# 11_-_CPU_-_POWER.net
KiCad netlist of a schematic drawn in Altium Designer
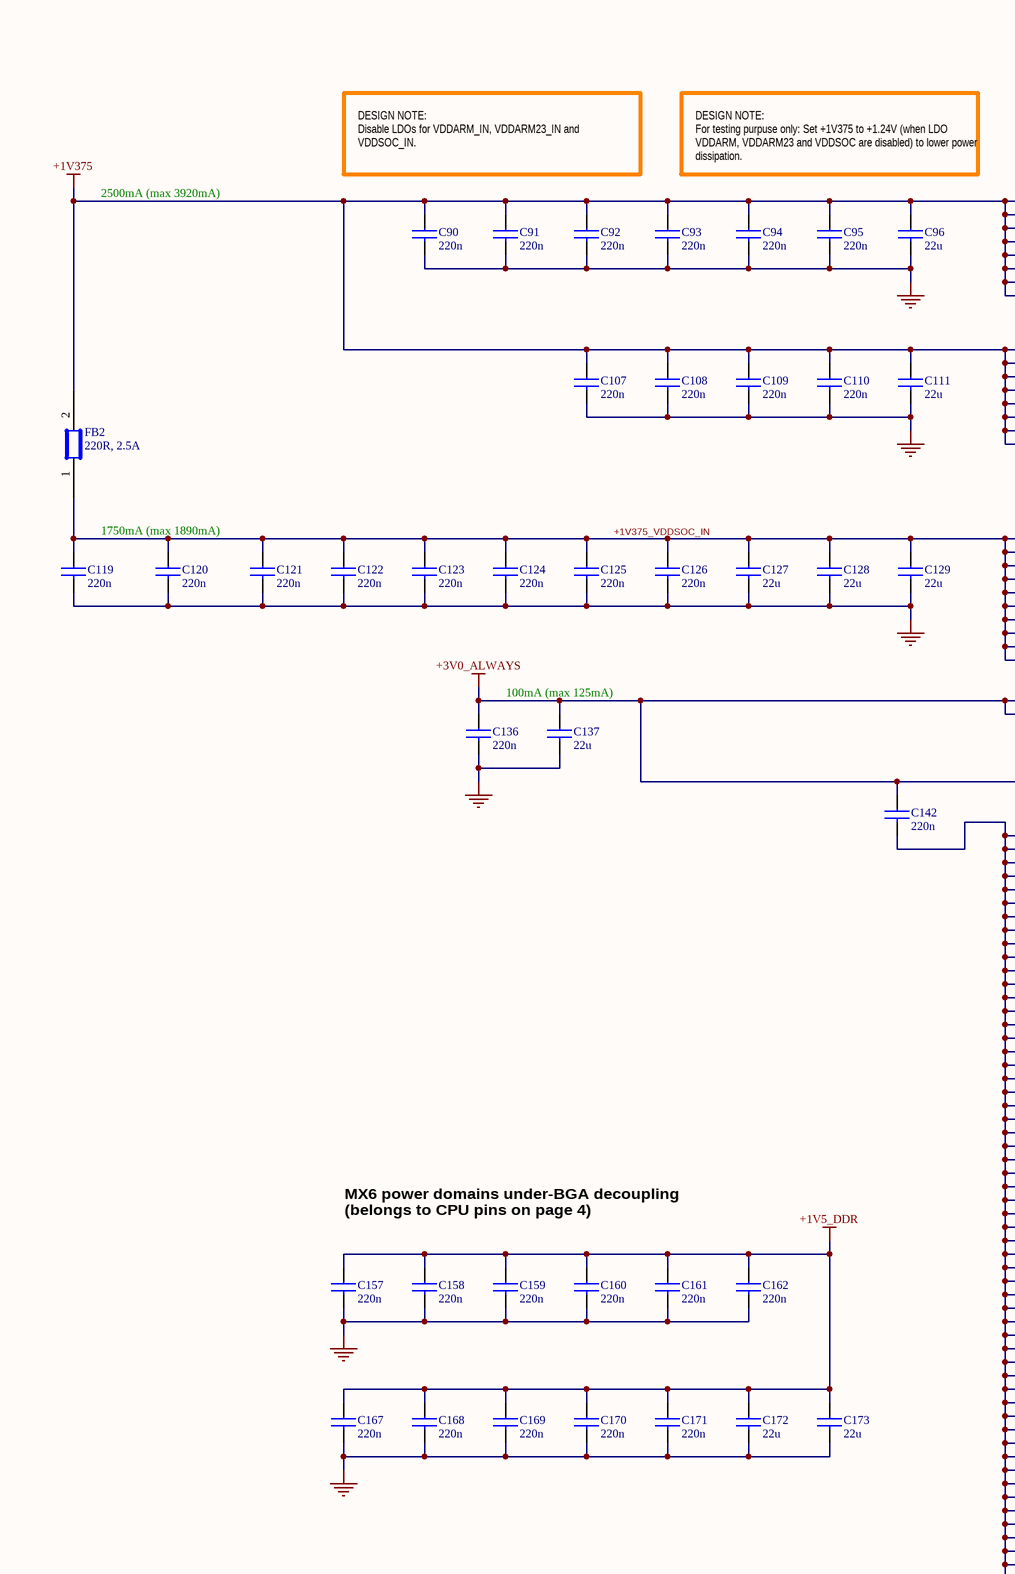
[diagram p0: [11] - CPU - POWER.SchDoc, left]
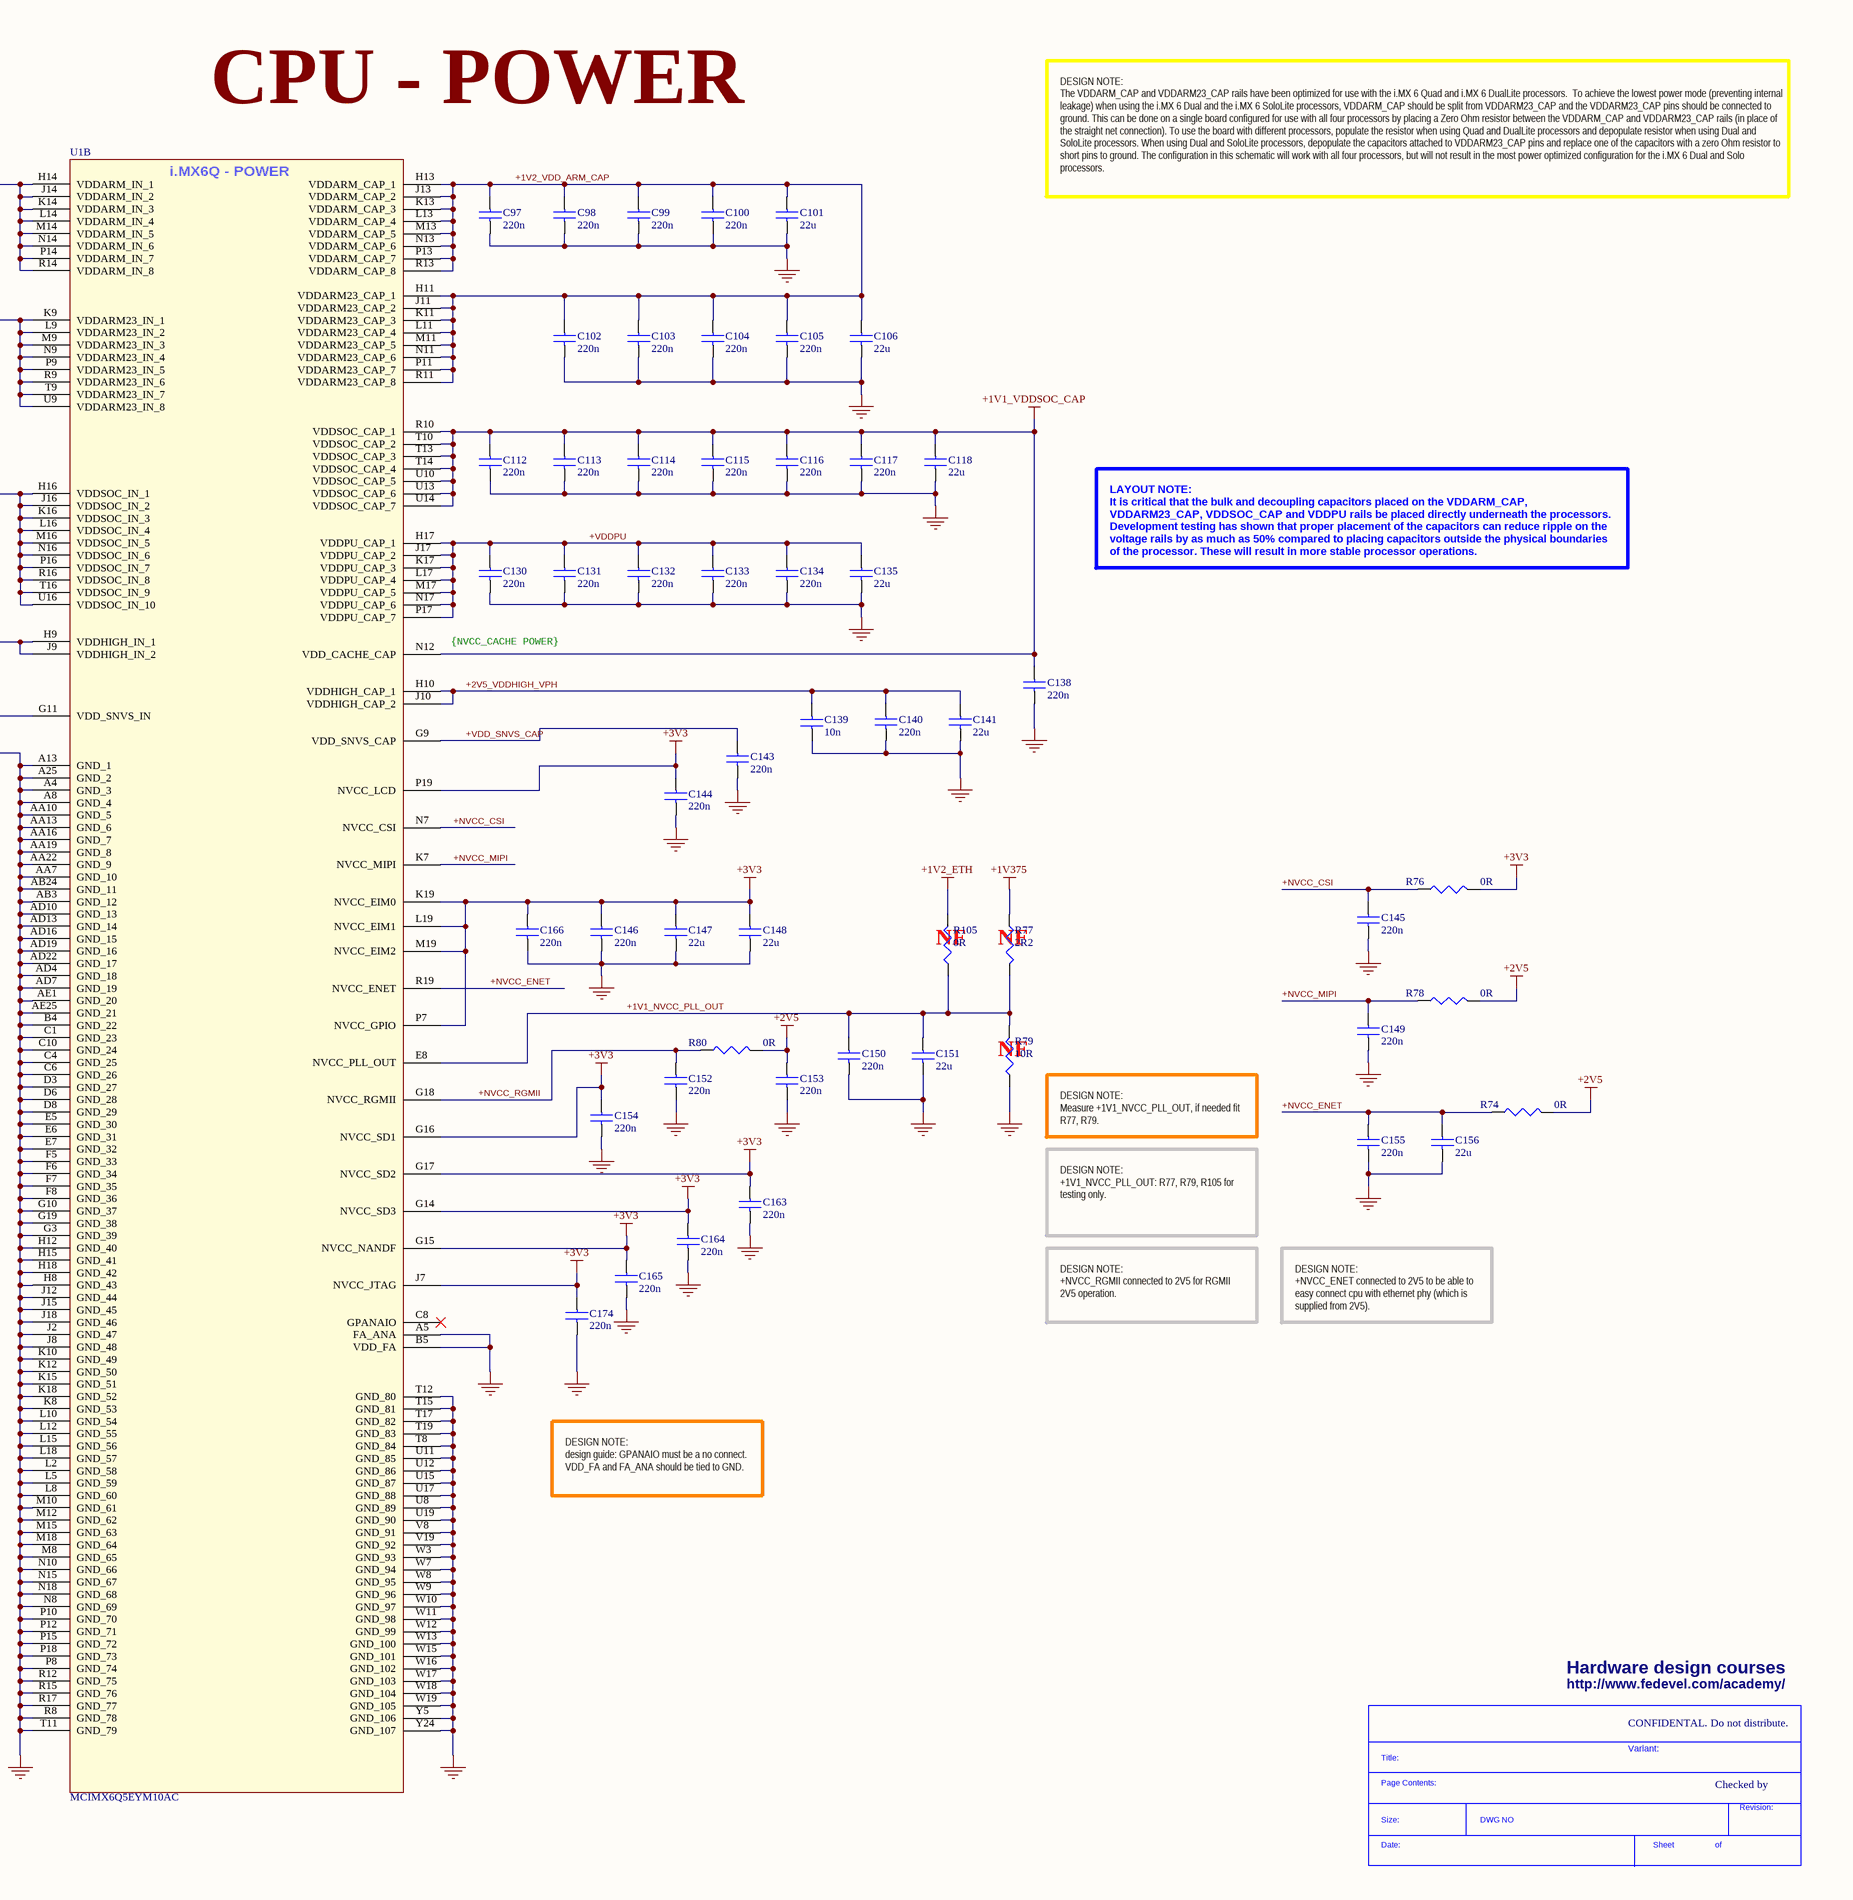
[diagram p1: [11] - CPU - POWER.SchDoc, right]

(export (version "E")
  (design (tool "Eeschema 10.0.6"))
  (components
    (comp (ref "C90")
      (value "220n")
      (footprint "C0402")
      (description "CAP CER .22UF 25V X5R 20% 0402")
      (fields
        (field (name "MANUFACTURER") "TDK Corporation")
        (field (name "MANUFACTURER PART NUMBER") "C1005X5R1E224M")
      )
      (libsource (lib "Integrated_Library_RF_FEB_2012") (part "C1005X5R1E224M"))
    )
    (comp (ref "C91")
      (value "220n")
      (footprint "C0402")
      (description "CAP CER .22UF 25V X5R 20% 0402")
      (fields
        (field (name "MANUFACTURER") "TDK Corporation")
        (field (name "MANUFACTURER PART NUMBER") "C1005X5R1E224M")
      )
      (libsource (lib "Integrated_Library_RF_FEB_2012") (part "C1005X5R1E224M"))
    )
    (comp (ref "C92")
      (value "220n")
      (footprint "C0402")
      (description "CAP CER .22UF 25V X5R 20% 0402")
      (fields
        (field (name "MANUFACTURER") "TDK Corporation")
        (field (name "MANUFACTURER PART NUMBER") "C1005X5R1E224M")
      )
      (libsource (lib "Integrated_Library_RF_FEB_2012") (part "C1005X5R1E224M"))
    )
    (comp (ref "C93")
      (value "220n")
      (footprint "C0402")
      (description "CAP CER .22UF 25V X5R 20% 0402")
      (fields
        (field (name "MANUFACTURER") "TDK Corporation")
        (field (name "MANUFACTURER PART NUMBER") "C1005X5R1E224M")
      )
      (libsource (lib "Integrated_Library_RF_FEB_2012") (part "C1005X5R1E224M"))
    )
    (comp (ref "C94")
      (value "220n")
      (footprint "C0402")
      (description "CAP CER .22UF 25V X5R 20% 0402")
      (fields
        (field (name "MANUFACTURER") "TDK Corporation")
        (field (name "MANUFACTURER PART NUMBER") "C1005X5R1E224M")
      )
      (libsource (lib "Integrated_Library_RF_FEB_2012") (part "C1005X5R1E224M"))
    )
    (comp (ref "C95")
      (value "220n")
      (footprint "C0402")
      (description "CAP CER .22UF 25V X5R 20% 0402")
      (fields
        (field (name "MANUFACTURER") "TDK Corporation")
        (field (name "MANUFACTURER PART NUMBER") "C1005X5R1E224M")
      )
      (libsource (lib "Integrated_Library_RF_FEB_2012") (part "C1005X5R1E224M"))
    )
    (comp (ref "C96")
      (value "22u")
      (footprint "C0603")
      (description "CAP CER 22UF 4V 20% X5R 0603")
      (fields
        (field (name "MANUFACTURER") "Murata Electronics North America")
        (field (name "MANUFACTURER PART NUMBER") "GRM188R60G226MEA0L")
        (field (name ".CHECKED PCB") "RF, used by MM")
        (field (name ".CHECKED SCH") "MM, checked by RF")
        (field (name ".CREATOR") "MM")
      )
      (libsource (lib "Schlib_RF") (part "GRM188R60G226MEA0L"))
    )
    (comp (ref "C97")
      (value "220n")
      (footprint "C0402")
      (description "CAP CER .22UF 25V X5R 20% 0402")
      (fields
        (field (name "MANUFACTURER") "TDK Corporation")
        (field (name "MANUFACTURER PART NUMBER") "C1005X5R1E224M")
      )
      (libsource (lib "Integrated_Library_RF_FEB_2012") (part "C1005X5R1E224M"))
    )
    (comp (ref "C98")
      (value "220n")
      (footprint "C0402")
      (description "CAP CER .22UF 25V X5R 20% 0402")
      (fields
        (field (name "MANUFACTURER") "TDK Corporation")
        (field (name "MANUFACTURER PART NUMBER") "C1005X5R1E224M")
      )
      (libsource (lib "Integrated_Library_RF_FEB_2012") (part "C1005X5R1E224M"))
    )
    (comp (ref "C99")
      (value "220n")
      (footprint "C0402")
      (description "CAP CER .22UF 25V X5R 20% 0402")
      (fields
        (field (name "MANUFACTURER") "TDK Corporation")
        (field (name "MANUFACTURER PART NUMBER") "C1005X5R1E224M")
      )
      (libsource (lib "Integrated_Library_RF_FEB_2012") (part "C1005X5R1E224M"))
    )
    (comp (ref "C100")
      (value "220n")
      (footprint "C0402")
      (description "CAP CER .22UF 25V X5R 20% 0402")
      (fields
        (field (name "MANUFACTURER") "TDK Corporation")
        (field (name "MANUFACTURER PART NUMBER") "C1005X5R1E224M")
      )
      (libsource (lib "Integrated_Library_RF_FEB_2012") (part "C1005X5R1E224M"))
    )
    (comp (ref "C101")
      (value "22u")
      (footprint "C0603")
      (description "CAP CER 22UF 4V 20% X5R 0603")
      (fields
        (field (name "MANUFACTURER") "Murata Electronics North America")
        (field (name "MANUFACTURER PART NUMBER") "GRM188R60G226MEA0L")
        (field (name ".CHECKED PCB") "RF, used by MM")
        (field (name ".CHECKED SCH") "MM, checked by RF")
        (field (name ".CREATOR") "MM")
      )
      (libsource (lib "Schlib_RF") (part "GRM188R60G226MEA0L"))
    )
    (comp (ref "C102")
      (value "220n")
      (footprint "C0402")
      (description "CAP CER .22UF 25V X5R 20% 0402")
      (fields
        (field (name "MANUFACTURER") "TDK Corporation")
        (field (name "MANUFACTURER PART NUMBER") "C1005X5R1E224M")
      )
      (libsource (lib "Integrated_Library_RF_FEB_2012") (part "C1005X5R1E224M"))
    )
    (comp (ref "C103")
      (value "220n")
      (footprint "C0402")
      (description "CAP CER .22UF 25V X5R 20% 0402")
      (fields
        (field (name "MANUFACTURER") "TDK Corporation")
        (field (name "MANUFACTURER PART NUMBER") "C1005X5R1E224M")
      )
      (libsource (lib "Integrated_Library_RF_FEB_2012") (part "C1005X5R1E224M"))
    )
    (comp (ref "C104")
      (value "220n")
      (footprint "C0402")
      (description "CAP CER .22UF 25V X5R 20% 0402")
      (fields
        (field (name "MANUFACTURER") "TDK Corporation")
        (field (name "MANUFACTURER PART NUMBER") "C1005X5R1E224M")
      )
      (libsource (lib "Integrated_Library_RF_FEB_2012") (part "C1005X5R1E224M"))
    )
    (comp (ref "C105")
      (value "220n")
      (footprint "C0402")
      (description "CAP CER .22UF 25V X5R 20% 0402")
      (fields
        (field (name "MANUFACTURER") "TDK Corporation")
        (field (name "MANUFACTURER PART NUMBER") "C1005X5R1E224M")
      )
      (libsource (lib "Integrated_Library_RF_FEB_2012") (part "C1005X5R1E224M"))
    )
    (comp (ref "C106")
      (value "22u")
      (footprint "C0603")
      (description "CAP CER 22UF 4V 20% X5R 0603")
      (fields
        (field (name "MANUFACTURER") "Murata Electronics North America")
        (field (name "MANUFACTURER PART NUMBER") "GRM188R60G226MEA0L")
        (field (name ".CHECKED PCB") "RF, used by MM")
        (field (name ".CHECKED SCH") "MM, checked by RF")
        (field (name ".CREATOR") "MM")
      )
      (libsource (lib "Schlib_RF") (part "GRM188R60G226MEA0L"))
    )
    (comp (ref "C107")
      (value "220n")
      (footprint "C0402")
      (description "CAP CER .22UF 25V X5R 20% 0402")
      (fields
        (field (name "MANUFACTURER") "TDK Corporation")
        (field (name "MANUFACTURER PART NUMBER") "C1005X5R1E224M")
      )
      (libsource (lib "Integrated_Library_RF_FEB_2012") (part "C1005X5R1E224M"))
    )
    (comp (ref "C108")
      (value "220n")
      (footprint "C0402")
      (description "CAP CER .22UF 25V X5R 20% 0402")
      (fields
        (field (name "MANUFACTURER") "TDK Corporation")
        (field (name "MANUFACTURER PART NUMBER") "C1005X5R1E224M")
      )
      (libsource (lib "Integrated_Library_RF_FEB_2012") (part "C1005X5R1E224M"))
    )
    (comp (ref "C109")
      (value "220n")
      (footprint "C0402")
      (description "CAP CER .22UF 25V X5R 20% 0402")
      (fields
        (field (name "MANUFACTURER") "TDK Corporation")
        (field (name "MANUFACTURER PART NUMBER") "C1005X5R1E224M")
      )
      (libsource (lib "Integrated_Library_RF_FEB_2012") (part "C1005X5R1E224M"))
    )
    (comp (ref "C110")
      (value "220n")
      (footprint "C0402")
      (description "CAP CER .22UF 25V X5R 20% 0402")
      (fields
        (field (name "MANUFACTURER") "TDK Corporation")
        (field (name "MANUFACTURER PART NUMBER") "C1005X5R1E224M")
      )
      (libsource (lib "Integrated_Library_RF_FEB_2012") (part "C1005X5R1E224M"))
    )
    (comp (ref "C111")
      (value "22u")
      (footprint "C0603")
      (description "CAP CER 22UF 4V 20% X5R 0603")
      (fields
        (field (name "MANUFACTURER") "Murata Electronics North America")
        (field (name "MANUFACTURER PART NUMBER") "GRM188R60G226MEA0L")
        (field (name ".CHECKED PCB") "RF, used by MM")
        (field (name ".CHECKED SCH") "MM, checked by RF")
        (field (name ".CREATOR") "MM")
      )
      (libsource (lib "Schlib_RF") (part "GRM188R60G226MEA0L"))
    )
    (comp (ref "C112")
      (value "220n")
      (footprint "C0402")
      (description "CAP CER .22UF 25V X5R 20% 0402")
      (fields
        (field (name "MANUFACTURER") "TDK Corporation")
        (field (name "MANUFACTURER PART NUMBER") "C1005X5R1E224M")
      )
      (libsource (lib "Integrated_Library_RF_FEB_2012") (part "C1005X5R1E224M"))
    )
    (comp (ref "C113")
      (value "220n")
      (footprint "C0402")
      (description "CAP CER .22UF 25V X5R 20% 0402")
      (fields
        (field (name "MANUFACTURER") "TDK Corporation")
        (field (name "MANUFACTURER PART NUMBER") "C1005X5R1E224M")
      )
      (libsource (lib "Integrated_Library_RF_FEB_2012") (part "C1005X5R1E224M"))
    )
    (comp (ref "C114")
      (value "220n")
      (footprint "C0402")
      (description "CAP CER .22UF 25V X5R 20% 0402")
      (fields
        (field (name "MANUFACTURER") "TDK Corporation")
        (field (name "MANUFACTURER PART NUMBER") "C1005X5R1E224M")
      )
      (libsource (lib "Integrated_Library_RF_FEB_2012") (part "C1005X5R1E224M"))
    )
    (comp (ref "C115")
      (value "220n")
      (footprint "C0402")
      (description "CAP CER .22UF 25V X5R 20% 0402")
      (fields
        (field (name "MANUFACTURER") "TDK Corporation")
        (field (name "MANUFACTURER PART NUMBER") "C1005X5R1E224M")
      )
      (libsource (lib "Integrated_Library_RF_FEB_2012") (part "C1005X5R1E224M"))
    )
    (comp (ref "C116")
      (value "220n")
      (footprint "C0402")
      (description "CAP CER .22UF 25V X5R 20% 0402")
      (fields
        (field (name "MANUFACTURER") "TDK Corporation")
        (field (name "MANUFACTURER PART NUMBER") "C1005X5R1E224M")
      )
      (libsource (lib "Integrated_Library_RF_FEB_2012") (part "C1005X5R1E224M"))
    )
    (comp (ref "C117")
      (value "220n")
      (footprint "C0402")
      (description "CAP CER .22UF 25V X5R 20% 0402")
      (fields
        (field (name "MANUFACTURER") "TDK Corporation")
        (field (name "MANUFACTURER PART NUMBER") "C1005X5R1E224M")
      )
      (libsource (lib "Integrated_Library_RF_FEB_2012") (part "C1005X5R1E224M"))
    )
    (comp (ref "C118")
      (value "22u")
      (footprint "C0603")
      (description "CAP CER 22UF 4V 20% X5R 0603")
      (fields
        (field (name "MANUFACTURER") "Murata Electronics North America")
        (field (name "MANUFACTURER PART NUMBER") "GRM188R60G226MEA0L")
        (field (name ".CHECKED PCB") "RF, used by MM")
        (field (name ".CHECKED SCH") "MM, checked by RF")
        (field (name ".CREATOR") "MM")
      )
      (libsource (lib "Schlib_RF") (part "GRM188R60G226MEA0L"))
    )
    (comp (ref "C119")
      (value "220n")
      (footprint "C0402")
      (description "CAP CER .22UF 25V X5R 20% 0402")
      (fields
        (field (name "MANUFACTURER") "TDK Corporation")
        (field (name "MANUFACTURER PART NUMBER") "C1005X5R1E224M")
      )
      (libsource (lib "Integrated_Library_RF_FEB_2012") (part "C1005X5R1E224M"))
    )
    (comp (ref "C120")
      (value "220n")
      (footprint "C0402")
      (description "CAP CER .22UF 25V X5R 20% 0402")
      (fields
        (field (name "MANUFACTURER") "TDK Corporation")
        (field (name "MANUFACTURER PART NUMBER") "C1005X5R1E224M")
      )
      (libsource (lib "Integrated_Library_RF_FEB_2012") (part "C1005X5R1E224M"))
    )
    (comp (ref "C121")
      (value "220n")
      (footprint "C0402")
      (description "CAP CER .22UF 25V X5R 20% 0402")
      (fields
        (field (name "MANUFACTURER") "TDK Corporation")
        (field (name "MANUFACTURER PART NUMBER") "C1005X5R1E224M")
      )
      (libsource (lib "Integrated_Library_RF_FEB_2012") (part "C1005X5R1E224M"))
    )
    (comp (ref "C122")
      (value "220n")
      (footprint "C0402")
      (description "CAP CER .22UF 25V X5R 20% 0402")
      (fields
        (field (name "MANUFACTURER") "TDK Corporation")
        (field (name "MANUFACTURER PART NUMBER") "C1005X5R1E224M")
      )
      (libsource (lib "Integrated_Library_RF_FEB_2012") (part "C1005X5R1E224M"))
    )
    (comp (ref "C123")
      (value "220n")
      (footprint "C0402")
      (description "CAP CER .22UF 25V X5R 20% 0402")
      (fields
        (field (name "MANUFACTURER") "TDK Corporation")
        (field (name "MANUFACTURER PART NUMBER") "C1005X5R1E224M")
      )
      (libsource (lib "Integrated_Library_RF_FEB_2012") (part "C1005X5R1E224M"))
    )
    (comp (ref "C124")
      (value "220n")
      (footprint "C0402")
      (description "CAP CER .22UF 25V X5R 20% 0402")
      (fields
        (field (name "MANUFACTURER") "TDK Corporation")
        (field (name "MANUFACTURER PART NUMBER") "C1005X5R1E224M")
      )
      (libsource (lib "Integrated_Library_RF_FEB_2012") (part "C1005X5R1E224M"))
    )
    (comp (ref "C125")
      (value "220n")
      (footprint "C0402")
      (description "CAP CER .22UF 25V X5R 20% 0402")
      (fields
        (field (name "MANUFACTURER") "TDK Corporation")
        (field (name "MANUFACTURER PART NUMBER") "C1005X5R1E224M")
      )
      (libsource (lib "Integrated_Library_RF_FEB_2012") (part "C1005X5R1E224M"))
    )
    (comp (ref "C126")
      (value "220n")
      (footprint "C0402")
      (description "CAP CER .22UF 25V X5R 20% 0402")
      (fields
        (field (name "MANUFACTURER") "TDK Corporation")
        (field (name "MANUFACTURER PART NUMBER") "C1005X5R1E224M")
      )
      (libsource (lib "Integrated_Library_RF_FEB_2012") (part "C1005X5R1E224M"))
    )
    (comp (ref "C127")
      (value "22u")
      (footprint "C0603")
      (description "CAP CER 22UF 4V 20% X5R 0603")
      (fields
        (field (name "MANUFACTURER") "Murata Electronics North America")
        (field (name "MANUFACTURER PART NUMBER") "GRM188R60G226MEA0L")
        (field (name ".CHECKED PCB") "RF, used by MM")
        (field (name ".CHECKED SCH") "MM, checked by RF")
        (field (name ".CREATOR") "MM")
      )
      (libsource (lib "Schlib_RF") (part "GRM188R60G226MEA0L"))
    )
    (comp (ref "C128")
      (value "22u")
      (footprint "C0603")
      (description "CAP CER 22UF 4V 20% X5R 0603")
      (fields
        (field (name "MANUFACTURER") "Murata Electronics North America")
        (field (name "MANUFACTURER PART NUMBER") "GRM188R60G226MEA0L")
        (field (name ".CHECKED PCB") "RF, used by MM")
        (field (name ".CHECKED SCH") "MM, checked by RF")
        (field (name ".CREATOR") "MM")
      )
      (libsource (lib "Schlib_RF") (part "GRM188R60G226MEA0L"))
    )
    (comp (ref "C129")
      (value "22u")
      (footprint "C0603")
      (description "CAP CER 22UF 4V 20% X5R 0603")
      (fields
        (field (name "MANUFACTURER") "Murata Electronics North America")
        (field (name "MANUFACTURER PART NUMBER") "GRM188R60G226MEA0L")
        (field (name ".CHECKED PCB") "RF, used by MM")
        (field (name ".CHECKED SCH") "MM, checked by RF")
        (field (name ".CREATOR") "MM")
      )
      (libsource (lib "Schlib_RF") (part "GRM188R60G226MEA0L"))
    )
    (comp (ref "C130")
      (value "220n")
      (footprint "C0402")
      (description "CAP CER .22UF 25V X5R 20% 0402")
      (fields
        (field (name "MANUFACTURER") "TDK Corporation")
        (field (name "MANUFACTURER PART NUMBER") "C1005X5R1E224M")
      )
      (libsource (lib "Integrated_Library_RF_FEB_2012") (part "C1005X5R1E224M"))
    )
    (comp (ref "C131")
      (value "220n")
      (footprint "C0402")
      (description "CAP CER .22UF 25V X5R 20% 0402")
      (fields
        (field (name "MANUFACTURER") "TDK Corporation")
        (field (name "MANUFACTURER PART NUMBER") "C1005X5R1E224M")
      )
      (libsource (lib "Integrated_Library_RF_FEB_2012") (part "C1005X5R1E224M"))
    )
    (comp (ref "C132")
      (value "220n")
      (footprint "C0402")
      (description "CAP CER .22UF 25V X5R 20% 0402")
      (fields
        (field (name "MANUFACTURER") "TDK Corporation")
        (field (name "MANUFACTURER PART NUMBER") "C1005X5R1E224M")
      )
      (libsource (lib "Integrated_Library_RF_FEB_2012") (part "C1005X5R1E224M"))
    )
    (comp (ref "C133")
      (value "220n")
      (footprint "C0402")
      (description "CAP CER .22UF 25V X5R 20% 0402")
      (fields
        (field (name "MANUFACTURER") "TDK Corporation")
        (field (name "MANUFACTURER PART NUMBER") "C1005X5R1E224M")
      )
      (libsource (lib "Integrated_Library_RF_FEB_2012") (part "C1005X5R1E224M"))
    )
    (comp (ref "C134")
      (value "220n")
      (footprint "C0402")
      (description "CAP CER .22UF 25V X5R 20% 0402")
      (fields
        (field (name "MANUFACTURER") "TDK Corporation")
        (field (name "MANUFACTURER PART NUMBER") "C1005X5R1E224M")
      )
      (libsource (lib "Integrated_Library_RF_FEB_2012") (part "C1005X5R1E224M"))
    )
    (comp (ref "C135")
      (value "22u")
      (footprint "C0603")
      (description "CAP CER 22UF 4V 20% X5R 0603")
      (fields
        (field (name "MANUFACTURER") "Murata Electronics North America")
        (field (name "MANUFACTURER PART NUMBER") "GRM188R60G226MEA0L")
        (field (name ".CHECKED PCB") "RF, used by MM")
        (field (name ".CHECKED SCH") "MM, checked by RF")
        (field (name ".CREATOR") "MM")
      )
      (libsource (lib "Schlib_RF") (part "GRM188R60G226MEA0L"))
    )
    (comp (ref "C136")
      (value "220n")
      (footprint "C0402")
      (description "CAP CER .22UF 25V X5R 20% 0402")
      (fields
        (field (name "MANUFACTURER") "TDK Corporation")
        (field (name "MANUFACTURER PART NUMBER") "C1005X5R1E224M")
      )
      (libsource (lib "Integrated_Library_RF_FEB_2012") (part "C1005X5R1E224M"))
    )
    (comp (ref "C137")
      (value "22u")
      (footprint "C0805")
      (description "CAP CER 22UF 16V 10% X5R 0805")
      (fields
        (field (name "MANUFACTURER") "TDK Corporation")
        (field (name "MANUFACTURER PART NUMBER") "C2012X5R1C226K")
        (field (name ".CHECKED PCB") "RF")
        (field (name ".CHECKED SCH") "RF")
      )
      (libsource (lib "Integrated_Library_RF_FEB_2012") (part "C2012X5R1C226K"))
    )
    (comp (ref "C138")
      (value "220n")
      (footprint "C0402")
      (description "CAP CER .22UF 25V X5R 20% 0402")
      (fields
        (field (name "MANUFACTURER") "TDK Corporation")
        (field (name "MANUFACTURER PART NUMBER") "C1005X5R1E224M")
      )
      (libsource (lib "Integrated_Library_RF_FEB_2012") (part "C1005X5R1E224M"))
    )
    (comp (ref "C139")
      (value "10n")
      (footprint "C0402")
      (description "CAP CER 10000PF 50V 10% X7R 0402")
      (fields
        (field (name "MANUFACTURER") "TDK Corporation")
        (field (name "MANUFACTURER PART NUMBER") "C1005X7R1H103K")
        (field (name ".CHECKED PCB") "RF")
        (field (name ".CHECKED SCH") "RF")
      )
      (libsource (lib "Integrated_Library_RF_FEB_2012") (part "C1005X7R1H103K"))
    )
    (comp (ref "C140")
      (value "220n")
      (footprint "C0402")
      (description "CAP CER .22UF 25V X5R 20% 0402")
      (fields
        (field (name "MANUFACTURER") "TDK Corporation")
        (field (name "MANUFACTURER PART NUMBER") "C1005X5R1E224M")
      )
      (libsource (lib "Integrated_Library_RF_FEB_2012") (part "C1005X5R1E224M"))
    )
    (comp (ref "C141")
      (value "22u")
      (footprint "C0805")
      (description "CAP CER 22UF 16V 10% X5R 0805")
      (fields
        (field (name "MANUFACTURER") "TDK Corporation")
        (field (name "MANUFACTURER PART NUMBER") "C2012X5R1C226K")
        (field (name ".CHECKED PCB") "RF")
        (field (name ".CHECKED SCH") "RF")
      )
      (libsource (lib "Integrated_Library_RF_FEB_2012") (part "C2012X5R1C226K"))
    )
    (comp (ref "C142")
      (value "220n")
      (footprint "C0402")
      (description "CAP CER .22UF 25V X5R 20% 0402")
      (fields
        (field (name "MANUFACTURER") "TDK Corporation")
        (field (name "MANUFACTURER PART NUMBER") "C1005X5R1E224M")
      )
      (libsource (lib "Integrated_Library_RF_FEB_2012") (part "C1005X5R1E224M"))
    )
    (comp (ref "C143")
      (value "220n")
      (footprint "C0402")
      (description "CAP CER .22UF 25V X5R 20% 0402")
      (fields
        (field (name "MANUFACTURER") "TDK Corporation")
        (field (name "MANUFACTURER PART NUMBER") "C1005X5R1E224M")
      )
      (libsource (lib "Integrated_Library_RF_FEB_2012") (part "C1005X5R1E224M"))
    )
    (comp (ref "C144")
      (value "220n")
      (footprint "C0402")
      (description "CAP CER .22UF 25V X5R 20% 0402")
      (fields
        (field (name "MANUFACTURER") "TDK Corporation")
        (field (name "MANUFACTURER PART NUMBER") "C1005X5R1E224M")
      )
      (libsource (lib "Integrated_Library_RF_FEB_2012") (part "C1005X5R1E224M"))
    )
    (comp (ref "C145")
      (value "220n")
      (footprint "C0402")
      (description "CAP CER .22UF 25V X5R 20% 0402")
      (fields
        (field (name "MANUFACTURER") "TDK Corporation")
        (field (name "MANUFACTURER PART NUMBER") "C1005X5R1E224M")
      )
      (libsource (lib "Integrated_Library_RF_FEB_2012") (part "C1005X5R1E224M"))
    )
    (comp (ref "C146")
      (value "220n")
      (footprint "C0402")
      (description "CAP CER .22UF 25V X5R 20% 0402")
      (fields
        (field (name "MANUFACTURER") "TDK Corporation")
        (field (name "MANUFACTURER PART NUMBER") "C1005X5R1E224M")
      )
      (libsource (lib "Integrated_Library_RF_FEB_2012") (part "C1005X5R1E224M"))
    )
    (comp (ref "C147")
      (value "22u")
      (footprint "C0805")
      (description "CAP CER 22UF 16V 10% X5R 0805")
      (fields
        (field (name "MANUFACTURER") "TDK Corporation")
        (field (name "MANUFACTURER PART NUMBER") "C2012X5R1C226K")
        (field (name ".CHECKED PCB") "RF")
        (field (name ".CHECKED SCH") "RF")
      )
      (libsource (lib "Integrated_Library_RF_FEB_2012") (part "C2012X5R1C226K"))
    )
    (comp (ref "C148")
      (value "22u")
      (footprint "C0805")
      (description "CAP CER 22UF 16V 10% X5R 0805")
      (fields
        (field (name "MANUFACTURER") "TDK Corporation")
        (field (name "MANUFACTURER PART NUMBER") "C2012X5R1C226K")
        (field (name ".CHECKED PCB") "RF")
        (field (name ".CHECKED SCH") "RF")
      )
      (libsource (lib "Integrated_Library_RF_FEB_2012") (part "C2012X5R1C226K"))
    )
    (comp (ref "C149")
      (value "220n")
      (footprint "C0402")
      (description "CAP CER .22UF 25V X5R 20% 0402")
      (fields
        (field (name "MANUFACTURER") "TDK Corporation")
        (field (name "MANUFACTURER PART NUMBER") "C1005X5R1E224M")
      )
      (libsource (lib "Integrated_Library_RF_FEB_2012") (part "C1005X5R1E224M"))
    )
    (comp (ref "C150")
      (value "220n")
      (footprint "C0402")
      (description "CAP CER .22UF 25V X5R 20% 0402")
      (fields
        (field (name "MANUFACTURER") "TDK Corporation")
        (field (name "MANUFACTURER PART NUMBER") "C1005X5R1E224M")
      )
      (libsource (lib "Integrated_Library_RF_FEB_2012") (part "C1005X5R1E224M"))
    )
    (comp (ref "C151")
      (value "22u")
      (footprint "C0603")
      (description "CAP CER 22UF 4V 20% X5R 0603")
      (fields
        (field (name "MANUFACTURER") "Murata Electronics North America")
        (field (name "MANUFACTURER PART NUMBER") "GRM188R60G226MEA0L")
        (field (name ".CHECKED PCB") "RF, used by MM")
        (field (name ".CHECKED SCH") "MM, checked by RF")
        (field (name ".CREATOR") "MM")
      )
      (libsource (lib "Schlib_RF") (part "GRM188R60G226MEA0L"))
    )
    (comp (ref "C152")
      (value "220n")
      (footprint "C0402")
      (description "CAP CER .22UF 25V X5R 20% 0402")
      (fields
        (field (name "MANUFACTURER") "TDK Corporation")
        (field (name "MANUFACTURER PART NUMBER") "C1005X5R1E224M")
      )
      (libsource (lib "Integrated_Library_RF_FEB_2012") (part "C1005X5R1E224M"))
    )
    (comp (ref "C153")
      (value "220n")
      (footprint "C0402")
      (description "CAP CER .22UF 25V X5R 20% 0402")
      (fields
        (field (name "MANUFACTURER") "TDK Corporation")
        (field (name "MANUFACTURER PART NUMBER") "C1005X5R1E224M")
      )
      (libsource (lib "Integrated_Library_RF_FEB_2012") (part "C1005X5R1E224M"))
    )
    (comp (ref "C154")
      (value "220n")
      (footprint "C0402")
      (description "CAP CER .22UF 25V X5R 20% 0402")
      (fields
        (field (name "MANUFACTURER") "TDK Corporation")
        (field (name "MANUFACTURER PART NUMBER") "C1005X5R1E224M")
      )
      (libsource (lib "Integrated_Library_RF_FEB_2012") (part "C1005X5R1E224M"))
    )
    (comp (ref "C155")
      (value "220n")
      (footprint "C0402")
      (description "CAP CER .22UF 25V X5R 20% 0402")
      (fields
        (field (name "MANUFACTURER") "TDK Corporation")
        (field (name "MANUFACTURER PART NUMBER") "C1005X5R1E224M")
      )
      (libsource (lib "Integrated_Library_RF_FEB_2012") (part "C1005X5R1E224M"))
    )
    (comp (ref "C156")
      (value "22u")
      (footprint "C0805")
      (description "CAP CER 22UF 16V 10% X5R 0805")
      (fields
        (field (name "MANUFACTURER") "TDK Corporation")
        (field (name "MANUFACTURER PART NUMBER") "C2012X5R1C226K")
        (field (name ".CHECKED PCB") "RF")
        (field (name ".CHECKED SCH") "RF")
      )
      (libsource (lib "Integrated_Library_RF_FEB_2012") (part "C2012X5R1C226K"))
    )
    (comp (ref "C157")
      (value "220n")
      (footprint "C0402")
      (description "CAP CER .22UF 25V X5R 20% 0402")
      (fields
        (field (name "MANUFACTURER") "TDK Corporation")
        (field (name "MANUFACTURER PART NUMBER") "C1005X5R1E224M")
      )
      (libsource (lib "Integrated_Library_RF_FEB_2012") (part "C1005X5R1E224M"))
    )
    (comp (ref "C158")
      (value "220n")
      (footprint "C0402")
      (description "CAP CER .22UF 25V X5R 20% 0402")
      (fields
        (field (name "MANUFACTURER") "TDK Corporation")
        (field (name "MANUFACTURER PART NUMBER") "C1005X5R1E224M")
      )
      (libsource (lib "Integrated_Library_RF_FEB_2012") (part "C1005X5R1E224M"))
    )
    (comp (ref "C159")
      (value "220n")
      (footprint "C0402")
      (description "CAP CER .22UF 25V X5R 20% 0402")
      (fields
        (field (name "MANUFACTURER") "TDK Corporation")
        (field (name "MANUFACTURER PART NUMBER") "C1005X5R1E224M")
      )
      (libsource (lib "Integrated_Library_RF_FEB_2012") (part "C1005X5R1E224M"))
    )
    (comp (ref "C160")
      (value "220n")
      (footprint "C0402")
      (description "CAP CER .22UF 25V X5R 20% 0402")
      (fields
        (field (name "MANUFACTURER") "TDK Corporation")
        (field (name "MANUFACTURER PART NUMBER") "C1005X5R1E224M")
      )
      (libsource (lib "Integrated_Library_RF_FEB_2012") (part "C1005X5R1E224M"))
    )
    (comp (ref "C161")
      (value "220n")
      (footprint "C0402")
      (description "CAP CER .22UF 25V X5R 20% 0402")
      (fields
        (field (name "MANUFACTURER") "TDK Corporation")
        (field (name "MANUFACTURER PART NUMBER") "C1005X5R1E224M")
      )
      (libsource (lib "Integrated_Library_RF_FEB_2012") (part "C1005X5R1E224M"))
    )
    (comp (ref "C162")
      (value "220n")
      (footprint "C0402")
      (description "CAP CER .22UF 25V X5R 20% 0402")
      (fields
        (field (name "MANUFACTURER") "TDK Corporation")
        (field (name "MANUFACTURER PART NUMBER") "C1005X5R1E224M")
      )
      (libsource (lib "Integrated_Library_RF_FEB_2012") (part "C1005X5R1E224M"))
    )
    (comp (ref "C163")
      (value "220n")
      (footprint "C0402")
      (description "CAP CER .22UF 25V X5R 20% 0402")
      (fields
        (field (name "MANUFACTURER") "TDK Corporation")
        (field (name "MANUFACTURER PART NUMBER") "C1005X5R1E224M")
      )
      (libsource (lib "Integrated_Library_RF_FEB_2012") (part "C1005X5R1E224M"))
    )
    (comp (ref "C164")
      (value "220n")
      (footprint "C0402")
      (description "CAP CER .22UF 25V X5R 20% 0402")
      (fields
        (field (name "MANUFACTURER") "TDK Corporation")
        (field (name "MANUFACTURER PART NUMBER") "C1005X5R1E224M")
      )
      (libsource (lib "Integrated_Library_RF_FEB_2012") (part "C1005X5R1E224M"))
    )
    (comp (ref "C165")
      (value "220n")
      (footprint "C0402")
      (description "CAP CER .22UF 25V X5R 20% 0402")
      (fields
        (field (name "MANUFACTURER") "TDK Corporation")
        (field (name "MANUFACTURER PART NUMBER") "C1005X5R1E224M")
      )
      (libsource (lib "Integrated_Library_RF_FEB_2012") (part "C1005X5R1E224M"))
    )
    (comp (ref "C166")
      (value "220n")
      (footprint "C0402")
      (description "CAP CER .22UF 25V X5R 20% 0402")
      (fields
        (field (name "MANUFACTURER") "TDK Corporation")
        (field (name "MANUFACTURER PART NUMBER") "C1005X5R1E224M")
      )
      (libsource (lib "Integrated_Library_RF_FEB_2012") (part "C1005X5R1E224M"))
    )
    (comp (ref "C167")
      (value "220n")
      (footprint "C0402")
      (description "CAP CER .22UF 25V X5R 20% 0402")
      (fields
        (field (name "MANUFACTURER") "TDK Corporation")
        (field (name "MANUFACTURER PART NUMBER") "C1005X5R1E224M")
      )
      (libsource (lib "Integrated_Library_RF_FEB_2012") (part "C1005X5R1E224M"))
    )
    (comp (ref "C168")
      (value "220n")
      (footprint "C0402")
      (description "CAP CER .22UF 25V X5R 20% 0402")
      (fields
        (field (name "MANUFACTURER") "TDK Corporation")
        (field (name "MANUFACTURER PART NUMBER") "C1005X5R1E224M")
      )
      (libsource (lib "Integrated_Library_RF_FEB_2012") (part "C1005X5R1E224M"))
    )
    (comp (ref "C169")
      (value "220n")
      (footprint "C0402")
      (description "CAP CER .22UF 25V X5R 20% 0402")
      (fields
        (field (name "MANUFACTURER") "TDK Corporation")
        (field (name "MANUFACTURER PART NUMBER") "C1005X5R1E224M")
      )
      (libsource (lib "Integrated_Library_RF_FEB_2012") (part "C1005X5R1E224M"))
    )
    (comp (ref "C170")
      (value "220n")
      (footprint "C0402")
      (description "CAP CER .22UF 25V X5R 20% 0402")
      (fields
        (field (name "MANUFACTURER") "TDK Corporation")
        (field (name "MANUFACTURER PART NUMBER") "C1005X5R1E224M")
      )
      (libsource (lib "Integrated_Library_RF_FEB_2012") (part "C1005X5R1E224M"))
    )
    (comp (ref "C171")
      (value "220n")
      (footprint "C0402")
      (description "CAP CER .22UF 25V X5R 20% 0402")
      (fields
        (field (name "MANUFACTURER") "TDK Corporation")
        (field (name "MANUFACTURER PART NUMBER") "C1005X5R1E224M")
      )
      (libsource (lib "Integrated_Library_RF_FEB_2012") (part "C1005X5R1E224M"))
    )
    (comp (ref "C172")
      (value "22u")
      (footprint "C0603")
      (description "CAP CER 22UF 4V 20% X5R 0603")
      (fields
        (field (name "MANUFACTURER") "Murata Electronics North America")
        (field (name "MANUFACTURER PART NUMBER") "GRM188R60G226MEA0L")
        (field (name ".CHECKED PCB") "RF, used by MM")
        (field (name ".CHECKED SCH") "MM, checked by RF")
        (field (name ".CREATOR") "MM")
      )
      (libsource (lib "Schlib_RF") (part "GRM188R60G226MEA0L"))
    )
    (comp (ref "C173")
      (value "22u")
      (footprint "C0603")
      (description "CAP CER 22UF 4V 20% X5R 0603")
      (fields
        (field (name "MANUFACTURER") "Murata Electronics North America")
        (field (name "MANUFACTURER PART NUMBER") "GRM188R60G226MEA0L")
        (field (name ".CHECKED PCB") "RF, used by MM")
        (field (name ".CHECKED SCH") "MM, checked by RF")
        (field (name ".CREATOR") "MM")
      )
      (libsource (lib "Schlib_RF") (part "GRM188R60G226MEA0L"))
    )
    (comp (ref "C174")
      (value "220n")
      (footprint "C0402")
      (description "CAP CER .22UF 25V X5R 20% 0402")
      (fields
        (field (name "MANUFACTURER") "TDK Corporation")
        (field (name "MANUFACTURER PART NUMBER") "C1005X5R1E224M")
      )
      (libsource (lib "Integrated_Library_RF_FEB_2012") (part "C1005X5R1E224M"))
    )
    (comp (ref "FB2")
      (value "220R, 2.5A")
      (footprint "C0603")
      (description "FERRITE CHIP 220 OHM 2500MA 0603")
      (fields
        (field (name "MANUFACTURER") "Murata Electronics North America")
        (field (name "MANUFACTURER PART NUMBER") "BLM18SG221TN1D")
        (field (name ".CHECKED PCB") "RF")
        (field (name ".CHECKED SCH") "RF")
      )
      (libsource (lib "Integrated_Library_RF_FEB_2012") (part "BLM18SG221TN1D"))
    )
    (comp (ref "R74")
      (value "0R")
      (footprint "R0402")
      (description "RES 0.0 OHM 1/16W 0402 SMD")
      (fields
        (field (name "MANUFACTURER") "Yageo")
        (field (name "MANUFACTURER PART NUMBER") "RC0402JR-070RL")
      )
      (libsource (lib "Integrated_Library_RF_FEB_2012") (part "RC0402JR-070RL"))
    )
    (comp (ref "R76")
      (value "0R")
      (footprint "R0402")
      (description "RES 0.0 OHM 1/16W 0402 SMD")
      (fields
        (field (name "MANUFACTURER") "Yageo")
        (field (name "MANUFACTURER PART NUMBER") "RC0402JR-070RL")
      )
      (libsource (lib "Integrated_Library_RF_FEB_2012") (part "RC0402JR-070RL"))
    )
    (comp (ref "R77")
      (value "2R2")
      (footprint "R0402")
      (description "RES 2.20 OHM 1/16W 1% 0402 SMD")
      (fields
        (field (name "MANUFACTURER") "Vishay Dale")
        (field (name "MANUFACTURER PART NUMBER") "CRCW04022R20FKED")
        (field (name ".CHECKED PCB") "RF")
        (field (name ".CHECKED SCH") "RF")
      )
      (libsource (lib "Integrated_Library_RF_FEB_2012") (part "CRCW04022R20FKED"))
    )
    (comp (ref "R78")
      (value "0R")
      (footprint "R0402")
      (description "RES 0.0 OHM 1/16W 0402 SMD")
      (fields
        (field (name "MANUFACTURER") "Yageo")
        (field (name "MANUFACTURER PART NUMBER") "RC0402JR-070RL")
      )
      (libsource (lib "Integrated_Library_RF_FEB_2012") (part "RC0402JR-070RL"))
    )
    (comp (ref "R79")
      (value "10R")
      (footprint "R0402")
      (description "RES 10.0 OHM 1/16W 1% 0402 SMD")
      (fields
        (field (name "MANUFACTURER") "Yageo")
        (field (name "MANUFACTURER PART NUMBER") "RC0402FR-0710RL")
      )
      (libsource (lib "Integrated_Library_RF_FEB_2012") (part "RC0402FR-0710RL"))
    )
    (comp (ref "R80")
      (value "0R")
      (footprint "R0402")
      (description "RES 0.0 OHM 1/16W 0402 SMD")
      (fields
        (field (name "MANUFACTURER") "Yageo")
        (field (name "MANUFACTURER PART NUMBER") "RC0402JR-070RL")
      )
      (libsource (lib "Integrated_Library_RF_FEB_2012") (part "RC0402JR-070RL"))
    )
    (comp (ref "R105")
      (value "0R")
      (footprint "R0402")
      (description "RES 0.0 OHM 1/16W 0402 SMD")
      (fields
        (field (name "MANUFACTURER") "Yageo")
        (field (name "MANUFACTURER PART NUMBER") "RC0402JR-070RL")
      )
      (libsource (lib "Integrated_Library_RF_FEB_2012") (part "RC0402JR-070RL"))
    )
    (comp (ref "U1")
      (value "MCIMX6Q5EYM10AC")
      (footprint "PBGA624")
      (description "IC MCU 32BIT ARM QUAD 624FCBGA")
      (fields
        (field (name "MANUFACTURER") "Freescale Semiconductor")
        (field (name ".CREATOR") "MM")
        (field (name ".CHECKED PCB") "MM, checked by RF")
        (field (name ".CHECKED SCH") "MM")
      )
      (libsource (lib "Schlib_RF") (part "MCIMX6Q5EYM10AC"))
    )
  )
  (nets
    (net (code "1") (name "+1V1_VDDSOC_CAP") (class "Default")
      (node (ref "C112") (pin "1") (pinfunction "1_1") (pintype "passive"))
      (node (ref "C113") (pin "1") (pinfunction "1_1") (pintype "passive"))
      (node (ref "C114") (pin "1") (pinfunction "1_1") (pintype "passive"))
      (node (ref "C115") (pin "1") (pinfunction "1_1") (pintype "passive"))
      (node (ref "C116") (pin "1") (pinfunction "1_1") (pintype "passive"))
      (node (ref "C117") (pin "1") (pinfunction "1_1") (pintype "passive"))
      (node (ref "C118") (pin "1") (pinfunction "1_1") (pintype "passive"))
      (node (ref "C138") (pin "1") (pinfunction "1_1") (pintype "passive"))
      (node (ref "U1") (pin "N12") (pinfunction "VDD_CACHE_CAP_N12") (pintype "power_in"))
      (node (ref "U1") (pin "R10") (pinfunction "VDDSOC_CAP_1_R10") (pintype "power_in"))
      (node (ref "U1") (pin "T10") (pinfunction "VDDSOC_CAP_2_T10") (pintype "power_in"))
      (node (ref "U1") (pin "T13") (pinfunction "VDDSOC_CAP_3_T13") (pintype "power_in"))
      (node (ref "U1") (pin "T14") (pinfunction "VDDSOC_CAP_4_T14") (pintype "power_in"))
      (node (ref "U1") (pin "U10") (pinfunction "VDDSOC_CAP_5_U10") (pintype "power_in"))
      (node (ref "U1") (pin "U13") (pinfunction "VDDSOC_CAP_6_U13") (pintype "power_in"))
      (node (ref "U1") (pin "U14") (pinfunction "VDDSOC_CAP_7_U14") (pintype "power_in"))
    )
    (net (code "2") (name "+1V2_ETH") (class "Default")
      (node (ref "R105") (pin "2") (pinfunction "2_2") (pintype "passive"))
    )
    (net (code "3") (name "+1V5_DDR") (class "Default")
      (node (ref "C157") (pin "1") (pinfunction "1_1") (pintype "passive"))
      (node (ref "C158") (pin "1") (pinfunction "1_1") (pintype "passive"))
      (node (ref "C159") (pin "1") (pinfunction "1_1") (pintype "passive"))
      (node (ref "C160") (pin "1") (pinfunction "1_1") (pintype "passive"))
      (node (ref "C161") (pin "1") (pinfunction "1_1") (pintype "passive"))
      (node (ref "C162") (pin "1") (pinfunction "1_1") (pintype "passive"))
      (node (ref "C167") (pin "1") (pinfunction "1_1") (pintype "passive"))
      (node (ref "C168") (pin "1") (pinfunction "1_1") (pintype "passive"))
      (node (ref "C169") (pin "1") (pinfunction "1_1") (pintype "passive"))
      (node (ref "C170") (pin "1") (pinfunction "1_1") (pintype "passive"))
      (node (ref "C171") (pin "1") (pinfunction "1_1") (pintype "passive"))
      (node (ref "C172") (pin "1") (pinfunction "1_1") (pintype "passive"))
      (node (ref "C173") (pin "1") (pinfunction "1_1") (pintype "passive"))
    )
    (net (code "4") (name "+1V375") (class "Default")
      (node (ref "C107") (pin "1") (pinfunction "1_1") (pintype "passive"))
      (node (ref "C108") (pin "1") (pinfunction "1_1") (pintype "passive"))
      (node (ref "C109") (pin "1") (pinfunction "1_1") (pintype "passive"))
      (node (ref "C110") (pin "1") (pinfunction "1_1") (pintype "passive"))
      (node (ref "C111") (pin "1") (pinfunction "1_1") (pintype "passive"))
      (node (ref "C90") (pin "1") (pinfunction "1_1") (pintype "passive"))
      (node (ref "C91") (pin "1") (pinfunction "1_1") (pintype "passive"))
      (node (ref "C92") (pin "1") (pinfunction "1_1") (pintype "passive"))
      (node (ref "C93") (pin "1") (pinfunction "1_1") (pintype "passive"))
      (node (ref "C94") (pin "1") (pinfunction "1_1") (pintype "passive"))
      (node (ref "C95") (pin "1") (pinfunction "1_1") (pintype "passive"))
      (node (ref "C96") (pin "1") (pinfunction "1_1") (pintype "passive"))
      (node (ref "FB2") (pin "2") (pinfunction "2_2") (pintype "passive"))
      (node (ref "R77") (pin "1") (pinfunction "1_1") (pintype "passive"))
      (node (ref "U1") (pin "H14") (pinfunction "VDDARM_IN_1_H14") (pintype "power_in"))
      (node (ref "U1") (pin "J14") (pinfunction "VDDARM_IN_2_J14") (pintype "power_in"))
      (node (ref "U1") (pin "K14") (pinfunction "VDDARM_IN_3_K14") (pintype "power_in"))
      (node (ref "U1") (pin "K9") (pinfunction "VDDARM23_IN_1_K9") (pintype "power_in"))
      (node (ref "U1") (pin "L14") (pinfunction "VDDARM_IN_4_L14") (pintype "power_in"))
      (node (ref "U1") (pin "L9") (pinfunction "VDDARM23_IN_2_L9") (pintype "power_in"))
      (node (ref "U1") (pin "M14") (pinfunction "VDDARM_IN_5_M14") (pintype "power_in"))
      (node (ref "U1") (pin "M9") (pinfunction "VDDARM23_IN_3_M9") (pintype "power_in"))
      (node (ref "U1") (pin "N14") (pinfunction "VDDARM_IN_6_N14") (pintype "power_in"))
      (node (ref "U1") (pin "N9") (pinfunction "VDDARM23_IN_4_N9") (pintype "power_in"))
      (node (ref "U1") (pin "P14") (pinfunction "VDDARM_IN_7_P14") (pintype "power_in"))
      (node (ref "U1") (pin "P9") (pinfunction "VDDARM23_IN_5_P9") (pintype "power_in"))
      (node (ref "U1") (pin "R14") (pinfunction "VDDARM_IN_8_R14") (pintype "power_in"))
      (node (ref "U1") (pin "R9") (pinfunction "VDDARM23_IN_6_R9") (pintype "power_in"))
      (node (ref "U1") (pin "T9") (pinfunction "VDDARM23_IN_7_T9") (pintype "power_in"))
      (node (ref "U1") (pin "U9") (pinfunction "VDDARM23_IN_8_U9") (pintype "power_in"))
    )
    (net (code "5") (name "+2V5") (class "Default")
      (node (ref "C153") (pin "1") (pinfunction "1_1") (pintype "passive"))
      (node (ref "R74") (pin "2") (pinfunction "2_2") (pintype "passive"))
      (node (ref "R78") (pin "2") (pinfunction "2_2") (pintype "passive"))
      (node (ref "R80") (pin "2") (pinfunction "2_2") (pintype "passive"))
    )
    (net (code "6") (name "+3V0_ALWAYS") (class "Default")
      (node (ref "C136") (pin "1") (pinfunction "1_1") (pintype "passive"))
      (node (ref "C137") (pin "1") (pinfunction "1_1") (pintype "passive"))
      (node (ref "C142") (pin "1") (pinfunction "1_1") (pintype "passive"))
      (node (ref "U1") (pin "G11") (pinfunction "VDD_SNVS_IN_G11") (pintype "power_in"))
      (node (ref "U1") (pin "H9") (pinfunction "VDDHIGH_IN_1_H9") (pintype "power_in"))
      (node (ref "U1") (pin "J9") (pinfunction "VDDHIGH_IN_2_J9") (pintype "power_in"))
    )
    (net (code "7") (name "+3V3") (class "Default")
      (node (ref "C144") (pin "1") (pinfunction "1_1") (pintype "passive"))
      (node (ref "C146") (pin "1") (pinfunction "1_1") (pintype "passive"))
      (node (ref "C147") (pin "1") (pinfunction "1_1") (pintype "passive"))
      (node (ref "C148") (pin "1") (pinfunction "1_1") (pintype "passive"))
      (node (ref "C154") (pin "1") (pinfunction "1_1") (pintype "passive"))
      (node (ref "C163") (pin "1") (pinfunction "1_1") (pintype "passive"))
      (node (ref "C164") (pin "1") (pinfunction "1_1") (pintype "passive"))
      (node (ref "C165") (pin "1") (pinfunction "1_1") (pintype "passive"))
      (node (ref "C166") (pin "1") (pinfunction "1_1") (pintype "passive"))
      (node (ref "C174") (pin "1") (pinfunction "1_1") (pintype "passive"))
      (node (ref "R76") (pin "2") (pinfunction "2_2") (pintype "passive"))
      (node (ref "U1") (pin "G14") (pinfunction "NVCC_SD3_G14") (pintype "power_in"))
      (node (ref "U1") (pin "G15") (pinfunction "NVCC_NANDF_G15") (pintype "power_in"))
      (node (ref "U1") (pin "G16") (pinfunction "NVCC_SD1_G16") (pintype "power_in"))
      (node (ref "U1") (pin "G17") (pinfunction "NVCC_SD2_G17") (pintype "power_in"))
      (node (ref "U1") (pin "J7") (pinfunction "NVCC_JTAG_J7") (pintype "power_in"))
      (node (ref "U1") (pin "K19") (pinfunction "NVCC_EIM0_K19") (pintype "power_in"))
      (node (ref "U1") (pin "L19") (pinfunction "NVCC_EIM1_L19") (pintype "power_in"))
      (node (ref "U1") (pin "M19") (pinfunction "NVCC_EIM2_M19") (pintype "power_in"))
      (node (ref "U1") (pin "P19") (pinfunction "NVCC_LCD_P19") (pintype "power_in"))
      (node (ref "U1") (pin "P7") (pinfunction "NVCC_GPIO_P7") (pintype "power_in"))
    )
    (net (code "8") (name "/+1V1_NVCC_PLL_OUT") (class "Default")
      (node (ref "C150") (pin "1") (pinfunction "1_1") (pintype "passive"))
      (node (ref "C151") (pin "1") (pinfunction "1_1") (pintype "passive"))
      (node (ref "R105") (pin "1") (pinfunction "1_1") (pintype "passive"))
      (node (ref "R77") (pin "2") (pinfunction "2_2") (pintype "passive"))
      (node (ref "R79") (pin "2") (pinfunction "2_2") (pintype "passive"))
      (node (ref "U1") (pin "E8") (pinfunction "NVCC_PLL_OUT_E8") (pintype "power_in"))
    )
    (net (code "9") (name "/+1V2_VDD_ARM_CAP") (class "Default")
      (node (ref "C100") (pin "1") (pinfunction "1_1") (pintype "passive"))
      (node (ref "C101") (pin "1") (pinfunction "1_1") (pintype "passive"))
      (node (ref "C102") (pin "1") (pinfunction "1_1") (pintype "passive"))
      (node (ref "C103") (pin "1") (pinfunction "1_1") (pintype "passive"))
      (node (ref "C104") (pin "1") (pinfunction "1_1") (pintype "passive"))
      (node (ref "C105") (pin "1") (pinfunction "1_1") (pintype "passive"))
      (node (ref "C106") (pin "1") (pinfunction "1_1") (pintype "passive"))
      (node (ref "C97") (pin "1") (pinfunction "1_1") (pintype "passive"))
      (node (ref "C98") (pin "1") (pinfunction "1_1") (pintype "passive"))
      (node (ref "C99") (pin "1") (pinfunction "1_1") (pintype "passive"))
      (node (ref "U1") (pin "H11") (pinfunction "VDDARM23_CAP_1_H11") (pintype "power_in"))
      (node (ref "U1") (pin "H13") (pinfunction "VDDARM_CAP_1_H13") (pintype "power_in"))
      (node (ref "U1") (pin "J11") (pinfunction "VDDARM23_CAP_2_J11") (pintype "power_in"))
      (node (ref "U1") (pin "J13") (pinfunction "VDDARM_CAP_2_J13") (pintype "power_in"))
      (node (ref "U1") (pin "K11") (pinfunction "VDDARM23_CAP_3_K11") (pintype "power_in"))
      (node (ref "U1") (pin "K13") (pinfunction "VDDARM_CAP_3_K13") (pintype "power_in"))
      (node (ref "U1") (pin "L11") (pinfunction "VDDARM23_CAP_4_L11") (pintype "power_in"))
      (node (ref "U1") (pin "L13") (pinfunction "VDDARM_CAP_4_L13") (pintype "power_in"))
      (node (ref "U1") (pin "M11") (pinfunction "VDDARM23_CAP_5_M11") (pintype "power_in"))
      (node (ref "U1") (pin "M13") (pinfunction "VDDARM_CAP_5_M13") (pintype "power_in"))
      (node (ref "U1") (pin "N11") (pinfunction "VDDARM23_CAP_6_N11") (pintype "power_in"))
      (node (ref "U1") (pin "N13") (pinfunction "VDDARM_CAP_6_N13") (pintype "power_in"))
      (node (ref "U1") (pin "P11") (pinfunction "VDDARM23_CAP_7_P11") (pintype "power_in"))
      (node (ref "U1") (pin "P13") (pinfunction "VDDARM_CAP_7_P13") (pintype "power_in"))
      (node (ref "U1") (pin "R11") (pinfunction "VDDARM23_CAP_8_R11") (pintype "power_in"))
      (node (ref "U1") (pin "R13") (pinfunction "VDDARM_CAP_8_R13") (pintype "power_in"))
    )
    (net (code "10") (name "/+1V375_VDDSOC_IN") (class "Default")
      (node (ref "C119") (pin "1") (pinfunction "1_1") (pintype "passive"))
      (node (ref "C120") (pin "1") (pinfunction "1_1") (pintype "passive"))
      (node (ref "C121") (pin "1") (pinfunction "1_1") (pintype "passive"))
      (node (ref "C122") (pin "1") (pinfunction "1_1") (pintype "passive"))
      (node (ref "C123") (pin "1") (pinfunction "1_1") (pintype "passive"))
      (node (ref "C124") (pin "1") (pinfunction "1_1") (pintype "passive"))
      (node (ref "C125") (pin "1") (pinfunction "1_1") (pintype "passive"))
      (node (ref "C126") (pin "1") (pinfunction "1_1") (pintype "passive"))
      (node (ref "C127") (pin "1") (pinfunction "1_1") (pintype "passive"))
      (node (ref "C128") (pin "1") (pinfunction "1_1") (pintype "passive"))
      (node (ref "C129") (pin "1") (pinfunction "1_1") (pintype "passive"))
      (node (ref "FB2") (pin "1") (pinfunction "1_1") (pintype "passive"))
      (node (ref "U1") (pin "H16") (pinfunction "VDDSOC_IN_1_H16") (pintype "power_in"))
      (node (ref "U1") (pin "J16") (pinfunction "VDDSOC_IN_2_J16") (pintype "power_in"))
      (node (ref "U1") (pin "K16") (pinfunction "VDDSOC_IN_3_K16") (pintype "power_in"))
      (node (ref "U1") (pin "L16") (pinfunction "VDDSOC_IN_4_L16") (pintype "power_in"))
      (node (ref "U1") (pin "M16") (pinfunction "VDDSOC_IN_5_M16") (pintype "power_in"))
      (node (ref "U1") (pin "N16") (pinfunction "VDDSOC_IN_6_N16") (pintype "power_in"))
      (node (ref "U1") (pin "P16") (pinfunction "VDDSOC_IN_7_P16") (pintype "power_in"))
      (node (ref "U1") (pin "R16") (pinfunction "VDDSOC_IN_8_R16") (pintype "power_in"))
      (node (ref "U1") (pin "T16") (pinfunction "VDDSOC_IN_9_T16") (pintype "power_in"))
      (node (ref "U1") (pin "U16") (pinfunction "VDDSOC_IN_10_U16") (pintype "power_in"))
    )
    (net (code "11") (name "/+2V5_VDDHIGH_VPH") (class "Default")
      (node (ref "C139") (pin "2") (pinfunction "2_2") (pintype "passive"))
      (node (ref "C140") (pin "1") (pinfunction "1_1") (pintype "passive"))
      (node (ref "C141") (pin "1") (pinfunction "1_1") (pintype "passive"))
      (node (ref "U1") (pin "H10") (pinfunction "VDDHIGH_CAP_1_H10") (pintype "power_in"))
      (node (ref "U1") (pin "J10") (pinfunction "VDDHIGH_CAP_2_J10") (pintype "power_in"))
    )
    (net (code "12") (name "/+NVCC_CSI") (class "Default")
      (node (ref "C145") (pin "1") (pinfunction "1_1") (pintype "passive"))
      (node (ref "R76") (pin "1") (pinfunction "1_1") (pintype "passive"))
      (node (ref "U1") (pin "N7") (pinfunction "NVCC_CSI_N7") (pintype "power_in"))
    )
    (net (code "13") (name "/+NVCC_ENET") (class "Default")
      (node (ref "C155") (pin "1") (pinfunction "1_1") (pintype "passive"))
      (node (ref "C156") (pin "1") (pinfunction "1_1") (pintype "passive"))
      (node (ref "R74") (pin "1") (pinfunction "1_1") (pintype "passive"))
      (node (ref "U1") (pin "R19") (pinfunction "NVCC_ENET_R19") (pintype "power_in"))
    )
    (net (code "14") (name "/+NVCC_MIPI") (class "Default")
      (node (ref "C149") (pin "1") (pinfunction "1_1") (pintype "passive"))
      (node (ref "R78") (pin "1") (pinfunction "1_1") (pintype "passive"))
      (node (ref "U1") (pin "K7") (pinfunction "NVCC_MIPI_K7") (pintype "power_in"))
    )
    (net (code "15") (name "/+NVCC_RGMII") (class "Default")
      (node (ref "C152") (pin "1") (pinfunction "1_1") (pintype "passive"))
      (node (ref "R80") (pin "1") (pinfunction "1_1") (pintype "passive"))
      (node (ref "U1") (pin "G18") (pinfunction "NVCC_RGMII_G18") (pintype "power_in"))
    )
    (net (code "16") (name "/+VDDPU") (class "Default")
      (node (ref "C130") (pin "1") (pinfunction "1_1") (pintype "passive"))
      (node (ref "C131") (pin "1") (pinfunction "1_1") (pintype "passive"))
      (node (ref "C132") (pin "1") (pinfunction "1_1") (pintype "passive"))
      (node (ref "C133") (pin "1") (pinfunction "1_1") (pintype "passive"))
      (node (ref "C134") (pin "1") (pinfunction "1_1") (pintype "passive"))
      (node (ref "C135") (pin "1") (pinfunction "1_1") (pintype "passive"))
      (node (ref "U1") (pin "H17") (pinfunction "VDDPU_CAP_1_H17") (pintype "power_in"))
      (node (ref "U1") (pin "J17") (pinfunction "VDDPU_CAP_2_J17") (pintype "power_in"))
      (node (ref "U1") (pin "K17") (pinfunction "VDDPU_CAP_3_K17") (pintype "power_in"))
      (node (ref "U1") (pin "L17") (pinfunction "VDDPU_CAP_4_L17") (pintype "power_in"))
      (node (ref "U1") (pin "M17") (pinfunction "VDDPU_CAP_5_M17") (pintype "power_in"))
      (node (ref "U1") (pin "N17") (pinfunction "VDDPU_CAP_6_N17") (pintype "power_in"))
      (node (ref "U1") (pin "P17") (pinfunction "VDDPU_CAP_7_P17") (pintype "power_in"))
    )
    (net (code "17") (name "/+VDD_SNVS_CAP") (class "Default")
      (node (ref "C143") (pin "1") (pinfunction "1_1") (pintype "passive"))
      (node (ref "U1") (pin "G9") (pinfunction "VDD_SNVS_CAP_G9") (pintype "power_in"))
    )
    (net (code "18") (name "GND") (class "Default")
      (node (ref "C100") (pin "2") (pinfunction "2_2") (pintype "passive"))
      (node (ref "C101") (pin "2") (pinfunction "2_2") (pintype "passive"))
      (node (ref "C102") (pin "2") (pinfunction "2_2") (pintype "passive"))
      (node (ref "C103") (pin "2") (pinfunction "2_2") (pintype "passive"))
      (node (ref "C104") (pin "2") (pinfunction "2_2") (pintype "passive"))
      (node (ref "C105") (pin "2") (pinfunction "2_2") (pintype "passive"))
      (node (ref "C106") (pin "2") (pinfunction "2_2") (pintype "passive"))
      (node (ref "C107") (pin "2") (pinfunction "2_2") (pintype "passive"))
      (node (ref "C108") (pin "2") (pinfunction "2_2") (pintype "passive"))
      (node (ref "C109") (pin "2") (pinfunction "2_2") (pintype "passive"))
      (node (ref "C110") (pin "2") (pinfunction "2_2") (pintype "passive"))
      (node (ref "C111") (pin "2") (pinfunction "2_2") (pintype "passive"))
      (node (ref "C112") (pin "2") (pinfunction "2_2") (pintype "passive"))
      (node (ref "C113") (pin "2") (pinfunction "2_2") (pintype "passive"))
      (node (ref "C114") (pin "2") (pinfunction "2_2") (pintype "passive"))
      (node (ref "C115") (pin "2") (pinfunction "2_2") (pintype "passive"))
      (node (ref "C116") (pin "2") (pinfunction "2_2") (pintype "passive"))
      (node (ref "C117") (pin "2") (pinfunction "2_2") (pintype "passive"))
      (node (ref "C118") (pin "2") (pinfunction "2_2") (pintype "passive"))
      (node (ref "C119") (pin "2") (pinfunction "2_2") (pintype "passive"))
      (node (ref "C120") (pin "2") (pinfunction "2_2") (pintype "passive"))
      (node (ref "C121") (pin "2") (pinfunction "2_2") (pintype "passive"))
      (node (ref "C122") (pin "2") (pinfunction "2_2") (pintype "passive"))
      (node (ref "C123") (pin "2") (pinfunction "2_2") (pintype "passive"))
      (node (ref "C124") (pin "2") (pinfunction "2_2") (pintype "passive"))
      (node (ref "C125") (pin "2") (pinfunction "2_2") (pintype "passive"))
      (node (ref "C126") (pin "2") (pinfunction "2_2") (pintype "passive"))
      (node (ref "C127") (pin "2") (pinfunction "2_2") (pintype "passive"))
      (node (ref "C128") (pin "2") (pinfunction "2_2") (pintype "passive"))
      (node (ref "C129") (pin "2") (pinfunction "2_2") (pintype "passive"))
      (node (ref "C130") (pin "2") (pinfunction "2_2") (pintype "passive"))
      (node (ref "C131") (pin "2") (pinfunction "2_2") (pintype "passive"))
      (node (ref "C132") (pin "2") (pinfunction "2_2") (pintype "passive"))
      (node (ref "C133") (pin "2") (pinfunction "2_2") (pintype "passive"))
      (node (ref "C134") (pin "2") (pinfunction "2_2") (pintype "passive"))
      (node (ref "C135") (pin "2") (pinfunction "2_2") (pintype "passive"))
      (node (ref "C136") (pin "2") (pinfunction "2_2") (pintype "passive"))
      (node (ref "C137") (pin "2") (pinfunction "2_2") (pintype "passive"))
      (node (ref "C138") (pin "2") (pinfunction "2_2") (pintype "passive"))
      (node (ref "C139") (pin "1") (pinfunction "1_1") (pintype "passive"))
      (node (ref "C140") (pin "2") (pinfunction "2_2") (pintype "passive"))
      (node (ref "C141") (pin "2") (pinfunction "2_2") (pintype "passive"))
      (node (ref "C142") (pin "2") (pinfunction "2_2") (pintype "passive"))
      (node (ref "C143") (pin "2") (pinfunction "2_2") (pintype "passive"))
      (node (ref "C144") (pin "2") (pinfunction "2_2") (pintype "passive"))
      (node (ref "C145") (pin "2") (pinfunction "2_2") (pintype "passive"))
      (node (ref "C146") (pin "2") (pinfunction "2_2") (pintype "passive"))
      (node (ref "C147") (pin "2") (pinfunction "2_2") (pintype "passive"))
      (node (ref "C148") (pin "2") (pinfunction "2_2") (pintype "passive"))
      (node (ref "C149") (pin "2") (pinfunction "2_2") (pintype "passive"))
      (node (ref "C150") (pin "2") (pinfunction "2_2") (pintype "passive"))
      (node (ref "C151") (pin "2") (pinfunction "2_2") (pintype "passive"))
      (node (ref "C152") (pin "2") (pinfunction "2_2") (pintype "passive"))
      (node (ref "C153") (pin "2") (pinfunction "2_2") (pintype "passive"))
      (node (ref "C154") (pin "2") (pinfunction "2_2") (pintype "passive"))
      (node (ref "C155") (pin "2") (pinfunction "2_2") (pintype "passive"))
      (node (ref "C156") (pin "2") (pinfunction "2_2") (pintype "passive"))
      (node (ref "C157") (pin "2") (pinfunction "2_2") (pintype "passive"))
      (node (ref "C158") (pin "2") (pinfunction "2_2") (pintype "passive"))
      (node (ref "C159") (pin "2") (pinfunction "2_2") (pintype "passive"))
      (node (ref "C160") (pin "2") (pinfunction "2_2") (pintype "passive"))
      (node (ref "C161") (pin "2") (pinfunction "2_2") (pintype "passive"))
      (node (ref "C162") (pin "2") (pinfunction "2_2") (pintype "passive"))
      (node (ref "C163") (pin "2") (pinfunction "2_2") (pintype "passive"))
      (node (ref "C164") (pin "2") (pinfunction "2_2") (pintype "passive"))
      (node (ref "C165") (pin "2") (pinfunction "2_2") (pintype "passive"))
      (node (ref "C166") (pin "2") (pinfunction "2_2") (pintype "passive"))
      (node (ref "C167") (pin "2") (pinfunction "2_2") (pintype "passive"))
      (node (ref "C168") (pin "2") (pinfunction "2_2") (pintype "passive"))
      (node (ref "C169") (pin "2") (pinfunction "2_2") (pintype "passive"))
      (node (ref "C170") (pin "2") (pinfunction "2_2") (pintype "passive"))
      (node (ref "C171") (pin "2") (pinfunction "2_2") (pintype "passive"))
      (node (ref "C172") (pin "2") (pinfunction "2_2") (pintype "passive"))
      (node (ref "C173") (pin "2") (pinfunction "2_2") (pintype "passive"))
      (node (ref "C174") (pin "2") (pinfunction "2_2") (pintype "passive"))
      (node (ref "C90") (pin "2") (pinfunction "2_2") (pintype "passive"))
      (node (ref "C91") (pin "2") (pinfunction "2_2") (pintype "passive"))
      (node (ref "C92") (pin "2") (pinfunction "2_2") (pintype "passive"))
      (node (ref "C93") (pin "2") (pinfunction "2_2") (pintype "passive"))
      (node (ref "C94") (pin "2") (pinfunction "2_2") (pintype "passive"))
      (node (ref "C95") (pin "2") (pinfunction "2_2") (pintype "passive"))
      (node (ref "C96") (pin "2") (pinfunction "2_2") (pintype "passive"))
      (node (ref "C97") (pin "2") (pinfunction "2_2") (pintype "passive"))
      (node (ref "C98") (pin "2") (pinfunction "2_2") (pintype "passive"))
      (node (ref "C99") (pin "2") (pinfunction "2_2") (pintype "passive"))
      (node (ref "R79") (pin "1") (pinfunction "1_1") (pintype "passive"))
      (node (ref "U1") (pin "A13") (pinfunction "GND_1_A13") (pintype "power_in"))
      (node (ref "U1") (pin "A25") (pinfunction "GND_2_A25") (pintype "power_in"))
      (node (ref "U1") (pin "A4") (pinfunction "GND_3_A4") (pintype "power_in"))
      (node (ref "U1") (pin "A5") (pinfunction "FA_ANA_A5") (pintype "power_in"))
      (node (ref "U1") (pin "A8") (pinfunction "GND_4_A8") (pintype "power_in"))
      (node (ref "U1") (pin "AA10") (pinfunction "GND_5_AA10") (pintype "power_in"))
      (node (ref "U1") (pin "AA13") (pinfunction "GND_6_AA13") (pintype "power_in"))
      (node (ref "U1") (pin "AA16") (pinfunction "GND_7_AA16") (pintype "power_in"))
      (node (ref "U1") (pin "AA19") (pinfunction "GND_8_AA19") (pintype "power_in"))
      (node (ref "U1") (pin "AA22") (pinfunction "GND_9_AA22") (pintype "power_in"))
      (node (ref "U1") (pin "AA7") (pinfunction "GND_10_AA7") (pintype "power_in"))
      (node (ref "U1") (pin "AB24") (pinfunction "GND_11_AB24") (pintype "power_in"))
      (node (ref "U1") (pin "AB3") (pinfunction "GND_12_AB3") (pintype "power_in"))
      (node (ref "U1") (pin "AD10") (pinfunction "GND_13_AD10") (pintype "power_in"))
      (node (ref "U1") (pin "AD13") (pinfunction "GND_14_AD13") (pintype "power_in"))
      (node (ref "U1") (pin "AD16") (pinfunction "GND_15_AD16") (pintype "power_in"))
      (node (ref "U1") (pin "AD19") (pinfunction "GND_16_AD19") (pintype "power_in"))
      (node (ref "U1") (pin "AD22") (pinfunction "GND_17_AD22") (pintype "power_in"))
      (node (ref "U1") (pin "AD4") (pinfunction "GND_18_AD4") (pintype "power_in"))
      (node (ref "U1") (pin "AD7") (pinfunction "GND_19_AD7") (pintype "power_in"))
      (node (ref "U1") (pin "AE1") (pinfunction "GND_20_AE1") (pintype "power_in"))
      (node (ref "U1") (pin "AE25") (pinfunction "GND_21_AE25") (pintype "power_in"))
      (node (ref "U1") (pin "B4") (pinfunction "GND_22_B4") (pintype "power_in"))
      (node (ref "U1") (pin "B5") (pinfunction "VDD_FA_B5") (pintype "power_in"))
      (node (ref "U1") (pin "C1") (pinfunction "GND_23_C1") (pintype "power_in"))
      (node (ref "U1") (pin "C10") (pinfunction "GND_24_C10") (pintype "power_in"))
      (node (ref "U1") (pin "C4") (pinfunction "GND_25_C4") (pintype "power_in"))
      (node (ref "U1") (pin "C6") (pinfunction "GND_26_C6") (pintype "power_in"))
      (node (ref "U1") (pin "D3") (pinfunction "GND_27_D3") (pintype "power_in"))
      (node (ref "U1") (pin "D6") (pinfunction "GND_28_D6") (pintype "power_in"))
      (node (ref "U1") (pin "D8") (pinfunction "GND_29_D8") (pintype "power_in"))
      (node (ref "U1") (pin "E5") (pinfunction "GND_30_E5") (pintype "power_in"))
      (node (ref "U1") (pin "E6") (pinfunction "GND_31_E6") (pintype "power_in"))
      (node (ref "U1") (pin "E7") (pinfunction "GND_32_E7") (pintype "power_in"))
      (node (ref "U1") (pin "F5") (pinfunction "GND_33_F5") (pintype "power_in"))
      (node (ref "U1") (pin "F6") (pinfunction "GND_34_F6") (pintype "power_in"))
      (node (ref "U1") (pin "F7") (pinfunction "GND_35_F7") (pintype "power_in"))
      (node (ref "U1") (pin "F8") (pinfunction "GND_36_F8") (pintype "power_in"))
      (node (ref "U1") (pin "G10") (pinfunction "GND_37_G10") (pintype "power_in"))
      (node (ref "U1") (pin "G19") (pinfunction "GND_38_G19") (pintype "power_in"))
      (node (ref "U1") (pin "G3") (pinfunction "GND_39_G3") (pintype "power_in"))
      (node (ref "U1") (pin "H12") (pinfunction "GND_40_H12") (pintype "power_in"))
      (node (ref "U1") (pin "H15") (pinfunction "GND_41_H15") (pintype "power_in"))
      (node (ref "U1") (pin "H18") (pinfunction "GND_42_H18") (pintype "power_in"))
      (node (ref "U1") (pin "H8") (pinfunction "GND_43_H8") (pintype "power_in"))
      (node (ref "U1") (pin "J12") (pinfunction "GND_44_J12") (pintype "power_in"))
      (node (ref "U1") (pin "J15") (pinfunction "GND_45_J15") (pintype "power_in"))
      (node (ref "U1") (pin "J18") (pinfunction "GND_46_J18") (pintype "power_in"))
      (node (ref "U1") (pin "J2") (pinfunction "GND_47_J2") (pintype "power_in"))
      (node (ref "U1") (pin "J8") (pinfunction "GND_48_J8") (pintype "power_in"))
      (node (ref "U1") (pin "K10") (pinfunction "GND_49_K10") (pintype "power_in"))
      (node (ref "U1") (pin "K12") (pinfunction "GND_50_K12") (pintype "power_in"))
      (node (ref "U1") (pin "K15") (pinfunction "GND_51_K15") (pintype "power_in"))
      (node (ref "U1") (pin "K18") (pinfunction "GND_52_K18") (pintype "power_in"))
      (node (ref "U1") (pin "K8") (pinfunction "GND_53_K8") (pintype "power_in"))
      (node (ref "U1") (pin "L10") (pinfunction "GND_54_L10") (pintype "power_in"))
      (node (ref "U1") (pin "L12") (pinfunction "GND_55_L12") (pintype "power_in"))
      (node (ref "U1") (pin "L15") (pinfunction "GND_56_L15") (pintype "power_in"))
      (node (ref "U1") (pin "L18") (pinfunction "GND_57_L18") (pintype "power_in"))
      (node (ref "U1") (pin "L2") (pinfunction "GND_58_L2") (pintype "power_in"))
      (node (ref "U1") (pin "L5") (pinfunction "GND_59_L5") (pintype "power_in"))
      (node (ref "U1") (pin "L8") (pinfunction "GND_60_L8") (pintype "power_in"))
      (node (ref "U1") (pin "M10") (pinfunction "GND_61_M10") (pintype "power_in"))
      (node (ref "U1") (pin "M12") (pinfunction "GND_62_M12") (pintype "power_in"))
      (node (ref "U1") (pin "M15") (pinfunction "GND_63_M15") (pintype "power_in"))
      (node (ref "U1") (pin "M18") (pinfunction "GND_64_M18") (pintype "power_in"))
      (node (ref "U1") (pin "M8") (pinfunction "GND_65_M8") (pintype "power_in"))
      (node (ref "U1") (pin "N10") (pinfunction "GND_66_N10") (pintype "power_in"))
      (node (ref "U1") (pin "N15") (pinfunction "GND_67_N15") (pintype "power_in"))
      (node (ref "U1") (pin "N18") (pinfunction "GND_68_N18") (pintype "power_in"))
      (node (ref "U1") (pin "N8") (pinfunction "GND_69_N8") (pintype "power_in"))
      (node (ref "U1") (pin "P10") (pinfunction "GND_70_P10") (pintype "power_in"))
      (node (ref "U1") (pin "P12") (pinfunction "GND_71_P12") (pintype "power_in"))
      (node (ref "U1") (pin "P15") (pinfunction "GND_72_P15") (pintype "power_in"))
      (node (ref "U1") (pin "P18") (pinfunction "GND_73_P18") (pintype "power_in"))
      (node (ref "U1") (pin "P8") (pinfunction "GND_74_P8") (pintype "power_in"))
      (node (ref "U1") (pin "R12") (pinfunction "GND_75_R12") (pintype "power_in"))
      (node (ref "U1") (pin "R15") (pinfunction "GND_76_R15") (pintype "power_in"))
      (node (ref "U1") (pin "R17") (pinfunction "GND_77_R17") (pintype "power_in"))
      (node (ref "U1") (pin "R8") (pinfunction "GND_78_R8") (pintype "power_in"))
      (node (ref "U1") (pin "T11") (pinfunction "GND_79_T11") (pintype "power_in"))
      (node (ref "U1") (pin "T12") (pinfunction "GND_80_T12") (pintype "power_in"))
      (node (ref "U1") (pin "T15") (pinfunction "GND_81_T15") (pintype "power_in"))
      (node (ref "U1") (pin "T17") (pinfunction "GND_82_T17") (pintype "power_in"))
      (node (ref "U1") (pin "T19") (pinfunction "GND_83_T19") (pintype "power_in"))
      (node (ref "U1") (pin "T8") (pinfunction "GND_84_T8") (pintype "power_in"))
      (node (ref "U1") (pin "U11") (pinfunction "GND_85_U11") (pintype "power_in"))
      (node (ref "U1") (pin "U12") (pinfunction "GND_86_U12") (pintype "power_in"))
      (node (ref "U1") (pin "U15") (pinfunction "GND_87_U15") (pintype "power_in"))
      (node (ref "U1") (pin "U17") (pinfunction "GND_88_U17") (pintype "power_in"))
      (node (ref "U1") (pin "U19") (pinfunction "GND_90_U19") (pintype "power_in"))
      (node (ref "U1") (pin "U8") (pinfunction "GND_89_U8") (pintype "power_in"))
      (node (ref "U1") (pin "V19") (pinfunction "GND_92_V19") (pintype "power_in"))
      (node (ref "U1") (pin "V8") (pinfunction "GND_91_V8") (pintype "power_in"))
      (node (ref "U1") (pin "W10") (pinfunction "GND_97_W10") (pintype "power_in"))
      (node (ref "U1") (pin "W11") (pinfunction "GND_98_W11") (pintype "power_in"))
      (node (ref "U1") (pin "W12") (pinfunction "GND_99_W12") (pintype "power_in"))
      (node (ref "U1") (pin "W13") (pinfunction "GND_100_W13") (pintype "power_in"))
      (node (ref "U1") (pin "W15") (pinfunction "GND_101_W15") (pintype "power_in"))
      (node (ref "U1") (pin "W16") (pinfunction "GND_102_W16") (pintype "power_in"))
      (node (ref "U1") (pin "W17") (pinfunction "GND_103_W17") (pintype "power_in"))
      (node (ref "U1") (pin "W18") (pinfunction "GND_104_W18") (pintype "power_in"))
      (node (ref "U1") (pin "W19") (pinfunction "GND_105_W19") (pintype "power_in"))
      (node (ref "U1") (pin "W3") (pinfunction "GND_93_W3") (pintype "power_in"))
      (node (ref "U1") (pin "W7") (pinfunction "GND_94_W7") (pintype "power_in"))
      (node (ref "U1") (pin "W8") (pinfunction "GND_95_W8") (pintype "power_in"))
      (node (ref "U1") (pin "W9") (pinfunction "GND_96_W9") (pintype "power_in"))
      (node (ref "U1") (pin "Y24") (pinfunction "GND_107_Y24") (pintype "power_in"))
      (node (ref "U1") (pin "Y5") (pinfunction "GND_106_Y5") (pintype "power_in"))
    )
    (net (code "19") (name "unconnected-(U1B-GPANAIO-PadC8)") (class "Default")
      (node (ref "U1") (pin "C8") (pinfunction "GPANAIO_C8") (pintype "power_in+no_connect"))
    )
  )
)
